# max10adc_v9_02_16chan_frontpanel.net
KiCad netlist of a schematic drawn in EAGLE
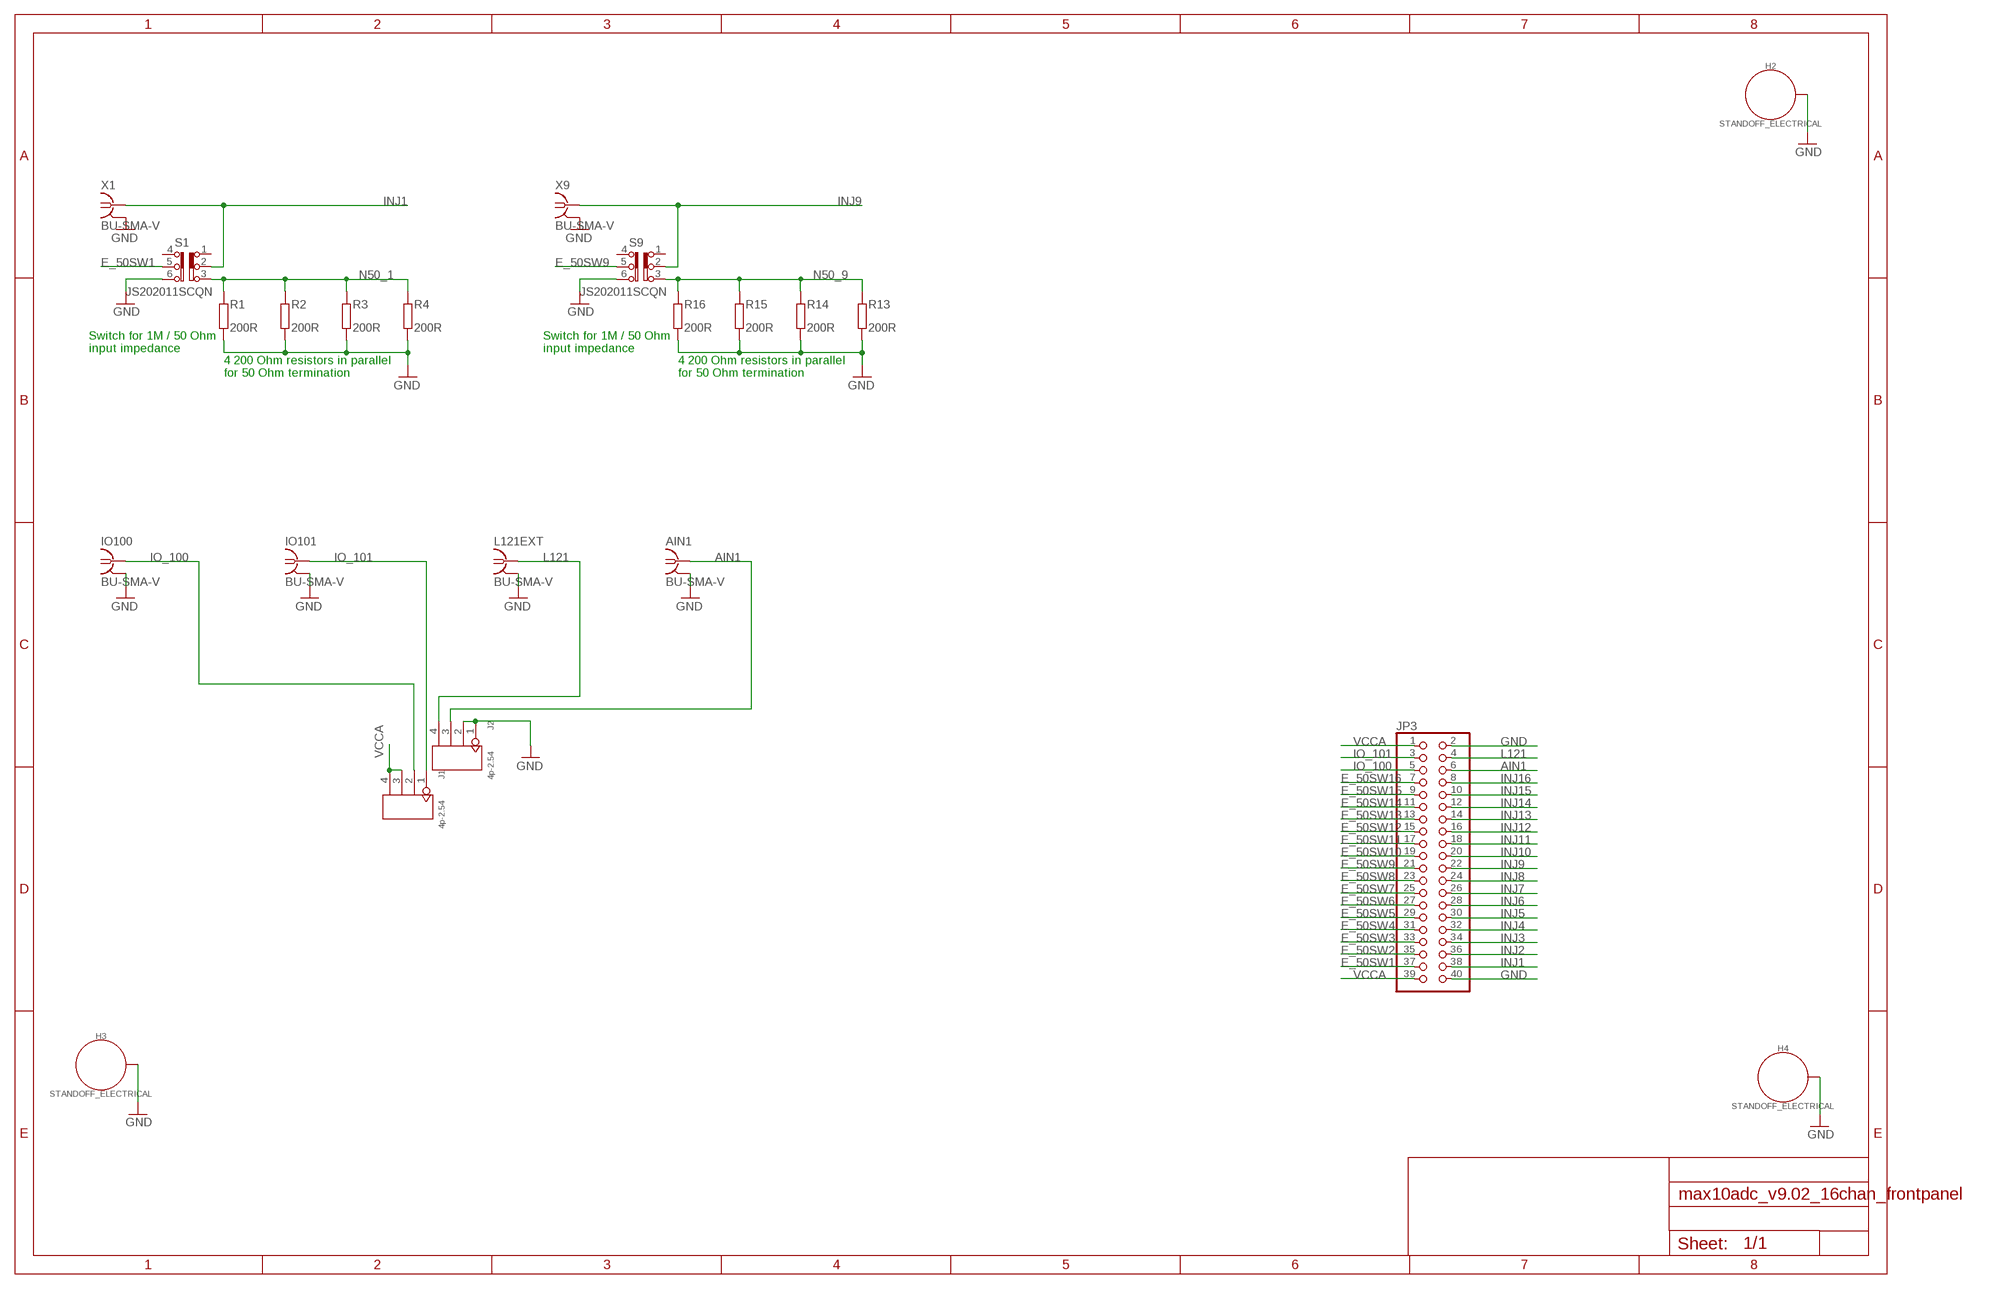
[diagram p0: schematic, sheet 1, part 1 of 2]
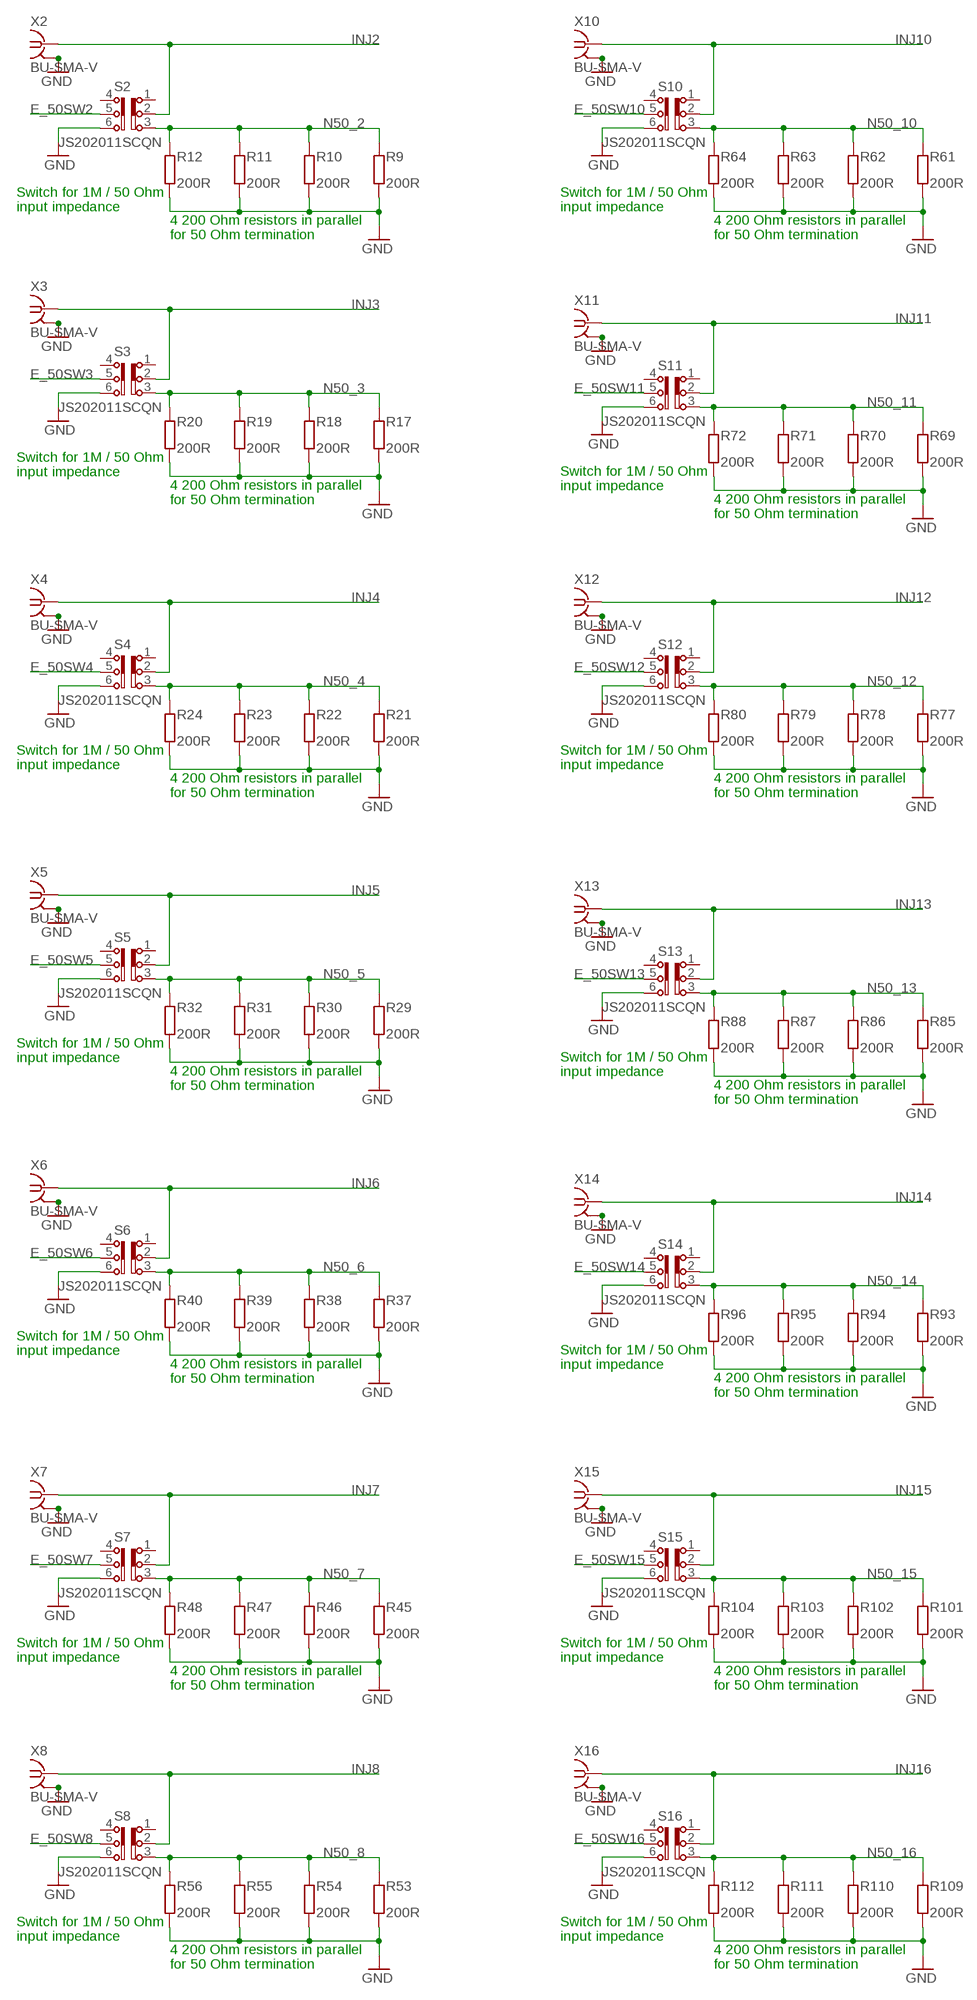
[diagram p1: schematic, sheet 1, part 2 of 2]

(export (version "E")
  (design (tool "Eeschema 10.0.6"))
  (components
    (comp (ref "AIN1")
      (value "BU-SMA-V")
      (footprint "eagle-import:BU-SMA-V")
      (libsource (lib "eagle-import") (part "BU-SMA-V"))
    )
    (comp (ref "H2")
      (value "STANDOFF_ELECTRICAL")
      (footprint "eagle-import:STANDOFF-ELECTRICAL")
      (libsource (lib "eagle-import") (part "STANDOFF_ELECTRICAL"))
    )
    (comp (ref "H3")
      (value "STANDOFF_ELECTRICAL")
      (footprint "eagle-import:STANDOFF-ELECTRICAL")
      (libsource (lib "eagle-import") (part "STANDOFF_ELECTRICAL"))
    )
    (comp (ref "H4")
      (value "STANDOFF_ELECTRICAL")
      (footprint "eagle-import:STANDOFF-ELECTRICAL")
      (libsource (lib "eagle-import") (part "STANDOFF_ELECTRICAL"))
    )
    (comp (ref "IO100")
      (value "BU-SMA-V")
      (footprint "eagle-import:BU-SMA-V")
      (libsource (lib "eagle-import") (part "BU-SMA-V"))
    )
    (comp (ref "IO101")
      (value "BU-SMA-V")
      (footprint "eagle-import:BU-SMA-V")
      (libsource (lib "eagle-import") (part "BU-SMA-V"))
    )
    (comp (ref "J1")
      (value "4p-2.54")
      (footprint "eagle-import:H4-2.54")
      (fields (field (name "MPN") "P125-1104A0BS116A1"))
      (libsource (lib "eagle-import") (part "DIP-BLACK-MALE-HEADER-VERT(4P-2.54)"))
    )
    (comp (ref "J2")
      (value "4p-2.54")
      (footprint "eagle-import:H4-2.54")
      (fields (field (name "MPN") "P125-1104A0BS116A1"))
      (libsource (lib "eagle-import") (part "DIP-BLACK-MALE-HEADER-VERT(4P-2.54)"))
    )
    (comp (ref "JP3")
      (value "PINHD-2X20")
      (footprint "eagle-import:2X20")
      (libsource (lib "eagle-import") (part "PINHD-2X20"))
    )
    (comp (ref "L121EXT")
      (value "BU-SMA-V")
      (footprint "eagle-import:BU-SMA-V")
      (libsource (lib "eagle-import") (part "BU-SMA-V"))
    )
    (comp (ref "R1")
      (value "200R")
      (footprint "eagle-import:R0805")
      (libsource (lib "eagle-import") (part "R-EU_R0805"))
    )
    (comp (ref "R2")
      (value "200R")
      (footprint "eagle-import:R0805")
      (libsource (lib "eagle-import") (part "R-EU_R0805"))
    )
    (comp (ref "R3")
      (value "200R")
      (footprint "eagle-import:R0805")
      (libsource (lib "eagle-import") (part "R-EU_R0805"))
    )
    (comp (ref "R4")
      (value "200R")
      (footprint "eagle-import:R0805")
      (libsource (lib "eagle-import") (part "R-EU_R0805"))
    )
    (comp (ref "R9")
      (value "200R")
      (footprint "eagle-import:R0805")
      (libsource (lib "eagle-import") (part "R-EU_R0805"))
    )
    (comp (ref "R10")
      (value "200R")
      (footprint "eagle-import:R0805")
      (libsource (lib "eagle-import") (part "R-EU_R0805"))
    )
    (comp (ref "R11")
      (value "200R")
      (footprint "eagle-import:R0805")
      (libsource (lib "eagle-import") (part "R-EU_R0805"))
    )
    (comp (ref "R12")
      (value "200R")
      (footprint "eagle-import:R0805")
      (libsource (lib "eagle-import") (part "R-EU_R0805"))
    )
    (comp (ref "R13")
      (value "200R")
      (footprint "eagle-import:R0805")
      (libsource (lib "eagle-import") (part "R-EU_R0805"))
    )
    (comp (ref "R14")
      (value "200R")
      (footprint "eagle-import:R0805")
      (libsource (lib "eagle-import") (part "R-EU_R0805"))
    )
    (comp (ref "R15")
      (value "200R")
      (footprint "eagle-import:R0805")
      (libsource (lib "eagle-import") (part "R-EU_R0805"))
    )
    (comp (ref "R16")
      (value "200R")
      (footprint "eagle-import:R0805")
      (libsource (lib "eagle-import") (part "R-EU_R0805"))
    )
    (comp (ref "R17")
      (value "200R")
      (footprint "eagle-import:R0805")
      (libsource (lib "eagle-import") (part "R-EU_R0805"))
    )
    (comp (ref "R18")
      (value "200R")
      (footprint "eagle-import:R0805")
      (libsource (lib "eagle-import") (part "R-EU_R0805"))
    )
    (comp (ref "R19")
      (value "200R")
      (footprint "eagle-import:R0805")
      (libsource (lib "eagle-import") (part "R-EU_R0805"))
    )
    (comp (ref "R20")
      (value "200R")
      (footprint "eagle-import:R0805")
      (libsource (lib "eagle-import") (part "R-EU_R0805"))
    )
    (comp (ref "R21")
      (value "200R")
      (footprint "eagle-import:R0805")
      (libsource (lib "eagle-import") (part "R-EU_R0805"))
    )
    (comp (ref "R22")
      (value "200R")
      (footprint "eagle-import:R0805")
      (libsource (lib "eagle-import") (part "R-EU_R0805"))
    )
    (comp (ref "R23")
      (value "200R")
      (footprint "eagle-import:R0805")
      (libsource (lib "eagle-import") (part "R-EU_R0805"))
    )
    (comp (ref "R24")
      (value "200R")
      (footprint "eagle-import:R0805")
      (libsource (lib "eagle-import") (part "R-EU_R0805"))
    )
    (comp (ref "R29")
      (value "200R")
      (footprint "eagle-import:R0805")
      (libsource (lib "eagle-import") (part "R-EU_R0805"))
    )
    (comp (ref "R30")
      (value "200R")
      (footprint "eagle-import:R0805")
      (libsource (lib "eagle-import") (part "R-EU_R0805"))
    )
    (comp (ref "R31")
      (value "200R")
      (footprint "eagle-import:R0805")
      (libsource (lib "eagle-import") (part "R-EU_R0805"))
    )
    (comp (ref "R32")
      (value "200R")
      (footprint "eagle-import:R0805")
      (libsource (lib "eagle-import") (part "R-EU_R0805"))
    )
    (comp (ref "R37")
      (value "200R")
      (footprint "eagle-import:R0805")
      (libsource (lib "eagle-import") (part "R-EU_R0805"))
    )
    (comp (ref "R38")
      (value "200R")
      (footprint "eagle-import:R0805")
      (libsource (lib "eagle-import") (part "R-EU_R0805"))
    )
    (comp (ref "R39")
      (value "200R")
      (footprint "eagle-import:R0805")
      (libsource (lib "eagle-import") (part "R-EU_R0805"))
    )
    (comp (ref "R40")
      (value "200R")
      (footprint "eagle-import:R0805")
      (libsource (lib "eagle-import") (part "R-EU_R0805"))
    )
    (comp (ref "R45")
      (value "200R")
      (footprint "eagle-import:R0805")
      (libsource (lib "eagle-import") (part "R-EU_R0805"))
    )
    (comp (ref "R46")
      (value "200R")
      (footprint "eagle-import:R0805")
      (libsource (lib "eagle-import") (part "R-EU_R0805"))
    )
    (comp (ref "R47")
      (value "200R")
      (footprint "eagle-import:R0805")
      (libsource (lib "eagle-import") (part "R-EU_R0805"))
    )
    (comp (ref "R48")
      (value "200R")
      (footprint "eagle-import:R0805")
      (libsource (lib "eagle-import") (part "R-EU_R0805"))
    )
    (comp (ref "R53")
      (value "200R")
      (footprint "eagle-import:R0805")
      (libsource (lib "eagle-import") (part "R-EU_R0805"))
    )
    (comp (ref "R54")
      (value "200R")
      (footprint "eagle-import:R0805")
      (libsource (lib "eagle-import") (part "R-EU_R0805"))
    )
    (comp (ref "R55")
      (value "200R")
      (footprint "eagle-import:R0805")
      (libsource (lib "eagle-import") (part "R-EU_R0805"))
    )
    (comp (ref "R56")
      (value "200R")
      (footprint "eagle-import:R0805")
      (libsource (lib "eagle-import") (part "R-EU_R0805"))
    )
    (comp (ref "R61")
      (value "200R")
      (footprint "eagle-import:R0805")
      (libsource (lib "eagle-import") (part "R-EU_R0805"))
    )
    (comp (ref "R62")
      (value "200R")
      (footprint "eagle-import:R0805")
      (libsource (lib "eagle-import") (part "R-EU_R0805"))
    )
    (comp (ref "R63")
      (value "200R")
      (footprint "eagle-import:R0805")
      (libsource (lib "eagle-import") (part "R-EU_R0805"))
    )
    (comp (ref "R64")
      (value "200R")
      (footprint "eagle-import:R0805")
      (libsource (lib "eagle-import") (part "R-EU_R0805"))
    )
    (comp (ref "R69")
      (value "200R")
      (footprint "eagle-import:R0805")
      (libsource (lib "eagle-import") (part "R-EU_R0805"))
    )
    (comp (ref "R70")
      (value "200R")
      (footprint "eagle-import:R0805")
      (libsource (lib "eagle-import") (part "R-EU_R0805"))
    )
    (comp (ref "R71")
      (value "200R")
      (footprint "eagle-import:R0805")
      (libsource (lib "eagle-import") (part "R-EU_R0805"))
    )
    (comp (ref "R72")
      (value "200R")
      (footprint "eagle-import:R0805")
      (libsource (lib "eagle-import") (part "R-EU_R0805"))
    )
    (comp (ref "R77")
      (value "200R")
      (footprint "eagle-import:R0805")
      (libsource (lib "eagle-import") (part "R-EU_R0805"))
    )
    (comp (ref "R78")
      (value "200R")
      (footprint "eagle-import:R0805")
      (libsource (lib "eagle-import") (part "R-EU_R0805"))
    )
    (comp (ref "R79")
      (value "200R")
      (footprint "eagle-import:R0805")
      (libsource (lib "eagle-import") (part "R-EU_R0805"))
    )
    (comp (ref "R80")
      (value "200R")
      (footprint "eagle-import:R0805")
      (libsource (lib "eagle-import") (part "R-EU_R0805"))
    )
    (comp (ref "R85")
      (value "200R")
      (footprint "eagle-import:R0805")
      (libsource (lib "eagle-import") (part "R-EU_R0805"))
    )
    (comp (ref "R86")
      (value "200R")
      (footprint "eagle-import:R0805")
      (libsource (lib "eagle-import") (part "R-EU_R0805"))
    )
    (comp (ref "R87")
      (value "200R")
      (footprint "eagle-import:R0805")
      (libsource (lib "eagle-import") (part "R-EU_R0805"))
    )
    (comp (ref "R88")
      (value "200R")
      (footprint "eagle-import:R0805")
      (libsource (lib "eagle-import") (part "R-EU_R0805"))
    )
    (comp (ref "R93")
      (value "200R")
      (footprint "eagle-import:R0805")
      (libsource (lib "eagle-import") (part "R-EU_R0805"))
    )
    (comp (ref "R94")
      (value "200R")
      (footprint "eagle-import:R0805")
      (libsource (lib "eagle-import") (part "R-EU_R0805"))
    )
    (comp (ref "R95")
      (value "200R")
      (footprint "eagle-import:R0805")
      (libsource (lib "eagle-import") (part "R-EU_R0805"))
    )
    (comp (ref "R96")
      (value "200R")
      (footprint "eagle-import:R0805")
      (libsource (lib "eagle-import") (part "R-EU_R0805"))
    )
    (comp (ref "R101")
      (value "200R")
      (footprint "eagle-import:R0805")
      (libsource (lib "eagle-import") (part "R-EU_R0805"))
    )
    (comp (ref "R102")
      (value "200R")
      (footprint "eagle-import:R0805")
      (libsource (lib "eagle-import") (part "R-EU_R0805"))
    )
    (comp (ref "R103")
      (value "200R")
      (footprint "eagle-import:R0805")
      (libsource (lib "eagle-import") (part "R-EU_R0805"))
    )
    (comp (ref "R104")
      (value "200R")
      (footprint "eagle-import:R0805")
      (libsource (lib "eagle-import") (part "R-EU_R0805"))
    )
    (comp (ref "R109")
      (value "200R")
      (footprint "eagle-import:R0805")
      (libsource (lib "eagle-import") (part "R-EU_R0805"))
    )
    (comp (ref "R110")
      (value "200R")
      (footprint "eagle-import:R0805")
      (libsource (lib "eagle-import") (part "R-EU_R0805"))
    )
    (comp (ref "R111")
      (value "200R")
      (footprint "eagle-import:R0805")
      (libsource (lib "eagle-import") (part "R-EU_R0805"))
    )
    (comp (ref "R112")
      (value "200R")
      (footprint "eagle-import:R0805")
      (libsource (lib "eagle-import") (part "R-EU_R0805"))
    )
    (comp (ref "S1")
      (value "JS202011SCQN")
      (footprint "eagle-import:JS202011SCQN")
      (libsource (lib "eagle-import") (part "JS202011SCQN"))
    )
    (comp (ref "S2")
      (value "JS202011SCQN")
      (footprint "eagle-import:JS202011SCQN")
      (libsource (lib "eagle-import") (part "JS202011SCQN"))
    )
    (comp (ref "S3")
      (value "JS202011SCQN")
      (footprint "eagle-import:JS202011SCQN")
      (libsource (lib "eagle-import") (part "JS202011SCQN"))
    )
    (comp (ref "S4")
      (value "JS202011SCQN")
      (footprint "eagle-import:JS202011SCQN")
      (libsource (lib "eagle-import") (part "JS202011SCQN"))
    )
    (comp (ref "S5")
      (value "JS202011SCQN")
      (footprint "eagle-import:JS202011SCQN")
      (libsource (lib "eagle-import") (part "JS202011SCQN"))
    )
    (comp (ref "S6")
      (value "JS202011SCQN")
      (footprint "eagle-import:JS202011SCQN")
      (libsource (lib "eagle-import") (part "JS202011SCQN"))
    )
    (comp (ref "S7")
      (value "JS202011SCQN")
      (footprint "eagle-import:JS202011SCQN")
      (libsource (lib "eagle-import") (part "JS202011SCQN"))
    )
    (comp (ref "S8")
      (value "JS202011SCQN")
      (footprint "eagle-import:JS202011SCQN")
      (libsource (lib "eagle-import") (part "JS202011SCQN"))
    )
    (comp (ref "S9")
      (value "JS202011SCQN")
      (footprint "eagle-import:JS202011SCQN")
      (libsource (lib "eagle-import") (part "JS202011SCQN"))
    )
    (comp (ref "S10")
      (value "JS202011SCQN")
      (footprint "eagle-import:JS202011SCQN")
      (libsource (lib "eagle-import") (part "JS202011SCQN"))
    )
    (comp (ref "S11")
      (value "JS202011SCQN")
      (footprint "eagle-import:JS202011SCQN")
      (libsource (lib "eagle-import") (part "JS202011SCQN"))
    )
    (comp (ref "S12")
      (value "JS202011SCQN")
      (footprint "eagle-import:JS202011SCQN")
      (libsource (lib "eagle-import") (part "JS202011SCQN"))
    )
    (comp (ref "S13")
      (value "JS202011SCQN")
      (footprint "eagle-import:JS202011SCQN")
      (libsource (lib "eagle-import") (part "JS202011SCQN"))
    )
    (comp (ref "S14")
      (value "JS202011SCQN")
      (footprint "eagle-import:JS202011SCQN")
      (libsource (lib "eagle-import") (part "JS202011SCQN"))
    )
    (comp (ref "S15")
      (value "JS202011SCQN")
      (footprint "eagle-import:JS202011SCQN")
      (libsource (lib "eagle-import") (part "JS202011SCQN"))
    )
    (comp (ref "S16")
      (value "JS202011SCQN")
      (footprint "eagle-import:JS202011SCQN")
      (libsource (lib "eagle-import") (part "JS202011SCQN"))
    )
    (comp (ref "X1")
      (value "BU-SMA-V")
      (footprint "eagle-import:BU-SMA-V")
      (libsource (lib "eagle-import") (part "BU-SMA-V"))
    )
    (comp (ref "X2")
      (value "BU-SMA-V")
      (footprint "eagle-import:BU-SMA-V")
      (libsource (lib "eagle-import") (part "BU-SMA-V"))
    )
    (comp (ref "X3")
      (value "BU-SMA-V")
      (footprint "eagle-import:BU-SMA-V")
      (libsource (lib "eagle-import") (part "BU-SMA-V"))
    )
    (comp (ref "X4")
      (value "BU-SMA-V")
      (footprint "eagle-import:BU-SMA-V")
      (libsource (lib "eagle-import") (part "BU-SMA-V"))
    )
    (comp (ref "X5")
      (value "BU-SMA-V")
      (footprint "eagle-import:BU-SMA-V")
      (libsource (lib "eagle-import") (part "BU-SMA-V"))
    )
    (comp (ref "X6")
      (value "BU-SMA-V")
      (footprint "eagle-import:BU-SMA-V")
      (libsource (lib "eagle-import") (part "BU-SMA-V"))
    )
    (comp (ref "X7")
      (value "BU-SMA-V")
      (footprint "eagle-import:BU-SMA-V")
      (libsource (lib "eagle-import") (part "BU-SMA-V"))
    )
    (comp (ref "X8")
      (value "BU-SMA-V")
      (footprint "eagle-import:BU-SMA-V")
      (libsource (lib "eagle-import") (part "BU-SMA-V"))
    )
    (comp (ref "X9")
      (value "BU-SMA-V")
      (footprint "eagle-import:BU-SMA-V")
      (libsource (lib "eagle-import") (part "BU-SMA-V"))
    )
    (comp (ref "X10")
      (value "BU-SMA-V")
      (footprint "eagle-import:BU-SMA-V")
      (libsource (lib "eagle-import") (part "BU-SMA-V"))
    )
    (comp (ref "X11")
      (value "BU-SMA-V")
      (footprint "eagle-import:BU-SMA-V")
      (libsource (lib "eagle-import") (part "BU-SMA-V"))
    )
    (comp (ref "X12")
      (value "BU-SMA-V")
      (footprint "eagle-import:BU-SMA-V")
      (libsource (lib "eagle-import") (part "BU-SMA-V"))
    )
    (comp (ref "X13")
      (value "BU-SMA-V")
      (footprint "eagle-import:BU-SMA-V")
      (libsource (lib "eagle-import") (part "BU-SMA-V"))
    )
    (comp (ref "X14")
      (value "BU-SMA-V")
      (footprint "eagle-import:BU-SMA-V")
      (libsource (lib "eagle-import") (part "BU-SMA-V"))
    )
    (comp (ref "X15")
      (value "BU-SMA-V")
      (footprint "eagle-import:BU-SMA-V")
      (libsource (lib "eagle-import") (part "BU-SMA-V"))
    )
    (comp (ref "X16")
      (value "BU-SMA-V")
      (footprint "eagle-import:BU-SMA-V")
      (libsource (lib "eagle-import") (part "BU-SMA-V"))
    )
  )
  (nets
    (net (code "1") (name "/AIN1") (class "Default")
      (node (ref "AIN1") (pin "1") (pinfunction "1_1") (pintype "passive"))
      (node (ref "J2") (pin "3") (pinfunction "P$3_3") (pintype "bidirectional"))
      (node (ref "JP3") (pin "6") (pinfunction "6_6") (pintype "passive"))
    )
    (net (code "2") (name "/E_50SW1") (class "Default")
      (node (ref "JP3") (pin "37") (pinfunction "37_37") (pintype "passive"))
      (node (ref "S1") (pin "5") (pinfunction "5_5") (pintype "passive"))
    )
    (net (code "3") (name "/E_50SW2") (class "Default")
      (node (ref "JP3") (pin "35") (pinfunction "35_35") (pintype "passive"))
      (node (ref "S2") (pin "5") (pinfunction "5_5") (pintype "passive"))
    )
    (net (code "4") (name "/E_50SW3") (class "Default")
      (node (ref "JP3") (pin "33") (pinfunction "33_33") (pintype "passive"))
      (node (ref "S3") (pin "5") (pinfunction "5_5") (pintype "passive"))
    )
    (net (code "5") (name "/E_50SW4") (class "Default")
      (node (ref "JP3") (pin "31") (pinfunction "31_31") (pintype "passive"))
      (node (ref "S4") (pin "5") (pinfunction "5_5") (pintype "passive"))
    )
    (net (code "6") (name "/E_50SW5") (class "Default")
      (node (ref "JP3") (pin "29") (pinfunction "29_29") (pintype "passive"))
      (node (ref "S5") (pin "5") (pinfunction "5_5") (pintype "passive"))
    )
    (net (code "7") (name "/E_50SW6") (class "Default")
      (node (ref "JP3") (pin "27") (pinfunction "27_27") (pintype "passive"))
      (node (ref "S6") (pin "5") (pinfunction "5_5") (pintype "passive"))
    )
    (net (code "8") (name "/E_50SW7") (class "Default")
      (node (ref "JP3") (pin "25") (pinfunction "25_25") (pintype "passive"))
      (node (ref "S7") (pin "5") (pinfunction "5_5") (pintype "passive"))
    )
    (net (code "9") (name "/E_50SW8") (class "Default")
      (node (ref "JP3") (pin "23") (pinfunction "23_23") (pintype "passive"))
      (node (ref "S8") (pin "5") (pinfunction "5_5") (pintype "passive"))
    )
    (net (code "10") (name "/E_50SW9") (class "Default")
      (node (ref "JP3") (pin "21") (pinfunction "21_21") (pintype "passive"))
      (node (ref "S9") (pin "5") (pinfunction "5_5") (pintype "passive"))
    )
    (net (code "11") (name "/E_50SW10") (class "Default")
      (node (ref "JP3") (pin "19") (pinfunction "19_19") (pintype "passive"))
      (node (ref "S10") (pin "5") (pinfunction "5_5") (pintype "passive"))
    )
    (net (code "12") (name "/E_50SW11") (class "Default")
      (node (ref "JP3") (pin "17") (pinfunction "17_17") (pintype "passive"))
      (node (ref "S11") (pin "5") (pinfunction "5_5") (pintype "passive"))
    )
    (net (code "13") (name "/E_50SW12") (class "Default")
      (node (ref "JP3") (pin "15") (pinfunction "15_15") (pintype "passive"))
      (node (ref "S12") (pin "5") (pinfunction "5_5") (pintype "passive"))
    )
    (net (code "14") (name "/E_50SW13") (class "Default")
      (node (ref "JP3") (pin "13") (pinfunction "13_13") (pintype "passive"))
      (node (ref "S13") (pin "5") (pinfunction "5_5") (pintype "passive"))
    )
    (net (code "15") (name "/E_50SW14") (class "Default")
      (node (ref "JP3") (pin "11") (pinfunction "11_11") (pintype "passive"))
      (node (ref "S14") (pin "5") (pinfunction "5_5") (pintype "passive"))
    )
    (net (code "16") (name "/E_50SW15") (class "Default")
      (node (ref "JP3") (pin "9") (pinfunction "9_9") (pintype "passive"))
      (node (ref "S15") (pin "5") (pinfunction "5_5") (pintype "passive"))
    )
    (net (code "17") (name "/E_50SW16") (class "Default")
      (node (ref "JP3") (pin "7") (pinfunction "7_7") (pintype "passive"))
      (node (ref "S16") (pin "5") (pinfunction "5_5") (pintype "passive"))
    )
    (net (code "18") (name "/INJ1") (class "Default")
      (node (ref "JP3") (pin "38") (pinfunction "38_38") (pintype "passive"))
      (node (ref "S1") (pin "2") (pinfunction "2_2") (pintype "passive"))
      (node (ref "X1") (pin "1") (pinfunction "1_1") (pintype "passive"))
    )
    (net (code "19") (name "/INJ2") (class "Default")
      (node (ref "JP3") (pin "36") (pinfunction "36_36") (pintype "passive"))
      (node (ref "S2") (pin "2") (pinfunction "2_2") (pintype "passive"))
      (node (ref "X2") (pin "1") (pinfunction "1_1") (pintype "passive"))
    )
    (net (code "20") (name "/INJ3") (class "Default")
      (node (ref "JP3") (pin "34") (pinfunction "34_34") (pintype "passive"))
      (node (ref "S3") (pin "2") (pinfunction "2_2") (pintype "passive"))
      (node (ref "X3") (pin "1") (pinfunction "1_1") (pintype "passive"))
    )
    (net (code "21") (name "/INJ4") (class "Default")
      (node (ref "JP3") (pin "32") (pinfunction "32_32") (pintype "passive"))
      (node (ref "S4") (pin "2") (pinfunction "2_2") (pintype "passive"))
      (node (ref "X4") (pin "1") (pinfunction "1_1") (pintype "passive"))
    )
    (net (code "22") (name "/INJ5") (class "Default")
      (node (ref "JP3") (pin "30") (pinfunction "30_30") (pintype "passive"))
      (node (ref "S5") (pin "2") (pinfunction "2_2") (pintype "passive"))
      (node (ref "X5") (pin "1") (pinfunction "1_1") (pintype "passive"))
    )
    (net (code "23") (name "/INJ6") (class "Default")
      (node (ref "JP3") (pin "28") (pinfunction "28_28") (pintype "passive"))
      (node (ref "S6") (pin "2") (pinfunction "2_2") (pintype "passive"))
      (node (ref "X6") (pin "1") (pinfunction "1_1") (pintype "passive"))
    )
    (net (code "24") (name "/INJ7") (class "Default")
      (node (ref "JP3") (pin "26") (pinfunction "26_26") (pintype "passive"))
      (node (ref "S7") (pin "2") (pinfunction "2_2") (pintype "passive"))
      (node (ref "X7") (pin "1") (pinfunction "1_1") (pintype "passive"))
    )
    (net (code "25") (name "/INJ8") (class "Default")
      (node (ref "JP3") (pin "24") (pinfunction "24_24") (pintype "passive"))
      (node (ref "S8") (pin "2") (pinfunction "2_2") (pintype "passive"))
      (node (ref "X8") (pin "1") (pinfunction "1_1") (pintype "passive"))
    )
    (net (code "26") (name "/INJ9") (class "Default")
      (node (ref "JP3") (pin "22") (pinfunction "22_22") (pintype "passive"))
      (node (ref "S9") (pin "2") (pinfunction "2_2") (pintype "passive"))
      (node (ref "X9") (pin "1") (pinfunction "1_1") (pintype "passive"))
    )
    (net (code "27") (name "/INJ10") (class "Default")
      (node (ref "JP3") (pin "20") (pinfunction "20_20") (pintype "passive"))
      (node (ref "S10") (pin "2") (pinfunction "2_2") (pintype "passive"))
      (node (ref "X10") (pin "1") (pinfunction "1_1") (pintype "passive"))
    )
    (net (code "28") (name "/INJ11") (class "Default")
      (node (ref "JP3") (pin "18") (pinfunction "18_18") (pintype "passive"))
      (node (ref "S11") (pin "2") (pinfunction "2_2") (pintype "passive"))
      (node (ref "X11") (pin "1") (pinfunction "1_1") (pintype "passive"))
    )
    (net (code "29") (name "/INJ12") (class "Default")
      (node (ref "JP3") (pin "16") (pinfunction "16_16") (pintype "passive"))
      (node (ref "S12") (pin "2") (pinfunction "2_2") (pintype "passive"))
      (node (ref "X12") (pin "1") (pinfunction "1_1") (pintype "passive"))
    )
    (net (code "30") (name "/INJ13") (class "Default")
      (node (ref "JP3") (pin "14") (pinfunction "14_14") (pintype "passive"))
      (node (ref "S13") (pin "2") (pinfunction "2_2") (pintype "passive"))
      (node (ref "X13") (pin "1") (pinfunction "1_1") (pintype "passive"))
    )
    (net (code "31") (name "/INJ14") (class "Default")
      (node (ref "JP3") (pin "12") (pinfunction "12_12") (pintype "passive"))
      (node (ref "S14") (pin "2") (pinfunction "2_2") (pintype "passive"))
      (node (ref "X14") (pin "1") (pinfunction "1_1") (pintype "passive"))
    )
    (net (code "32") (name "/INJ15") (class "Default")
      (node (ref "JP3") (pin "10") (pinfunction "10_10") (pintype "passive"))
      (node (ref "S15") (pin "2") (pinfunction "2_2") (pintype "passive"))
      (node (ref "X15") (pin "1") (pinfunction "1_1") (pintype "passive"))
    )
    (net (code "33") (name "/INJ16") (class "Default")
      (node (ref "JP3") (pin "8") (pinfunction "8_8") (pintype "passive"))
      (node (ref "S16") (pin "2") (pinfunction "2_2") (pintype "passive"))
      (node (ref "X16") (pin "1") (pinfunction "1_1") (pintype "passive"))
    )
    (net (code "34") (name "/IO_100") (class "Default")
      (node (ref "IO100") (pin "1") (pinfunction "1_1") (pintype "passive"))
      (node (ref "J1") (pin "2") (pinfunction "P$2_2") (pintype "bidirectional"))
      (node (ref "JP3") (pin "5") (pinfunction "5_5") (pintype "passive"))
    )
    (net (code "35") (name "/IO_101") (class "Default")
      (node (ref "IO101") (pin "1") (pinfunction "1_1") (pintype "passive"))
      (node (ref "J1") (pin "1") (pinfunction "P$1_1") (pintype "bidirectional"))
      (node (ref "JP3") (pin "3") (pinfunction "3_3") (pintype "passive"))
    )
    (net (code "36") (name "/L121") (class "Default")
      (node (ref "J2") (pin "4") (pinfunction "P$4_4") (pintype "bidirectional"))
      (node (ref "JP3") (pin "4") (pinfunction "4_4") (pintype "passive"))
      (node (ref "L121EXT") (pin "1") (pinfunction "1_1") (pintype "passive"))
    )
    (net (code "37") (name "/N50_1") (class "Default")
      (node (ref "R1") (pin "1") (pinfunction "1_1") (pintype "passive"))
      (node (ref "R2") (pin "1") (pinfunction "1_1") (pintype "passive"))
      (node (ref "R3") (pin "1") (pinfunction "1_1") (pintype "passive"))
      (node (ref "R4") (pin "1") (pinfunction "1_1") (pintype "passive"))
      (node (ref "S1") (pin "3") (pinfunction "3_3") (pintype "passive"))
    )
    (net (code "38") (name "/N50_2") (class "Default")
      (node (ref "R10") (pin "1") (pinfunction "1_1") (pintype "passive"))
      (node (ref "R11") (pin "1") (pinfunction "1_1") (pintype "passive"))
      (node (ref "R12") (pin "1") (pinfunction "1_1") (pintype "passive"))
      (node (ref "R9") (pin "1") (pinfunction "1_1") (pintype "passive"))
      (node (ref "S2") (pin "3") (pinfunction "3_3") (pintype "passive"))
    )
    (net (code "39") (name "/N50_3") (class "Default")
      (node (ref "R17") (pin "1") (pinfunction "1_1") (pintype "passive"))
      (node (ref "R18") (pin "1") (pinfunction "1_1") (pintype "passive"))
      (node (ref "R19") (pin "1") (pinfunction "1_1") (pintype "passive"))
      (node (ref "R20") (pin "1") (pinfunction "1_1") (pintype "passive"))
      (node (ref "S3") (pin "3") (pinfunction "3_3") (pintype "passive"))
    )
    (net (code "40") (name "/N50_4") (class "Default")
      (node (ref "R21") (pin "1") (pinfunction "1_1") (pintype "passive"))
      (node (ref "R22") (pin "1") (pinfunction "1_1") (pintype "passive"))
      (node (ref "R23") (pin "1") (pinfunction "1_1") (pintype "passive"))
      (node (ref "R24") (pin "1") (pinfunction "1_1") (pintype "passive"))
      (node (ref "S4") (pin "3") (pinfunction "3_3") (pintype "passive"))
    )
    (net (code "41") (name "/N50_5") (class "Default")
      (node (ref "R29") (pin "1") (pinfunction "1_1") (pintype "passive"))
      (node (ref "R30") (pin "1") (pinfunction "1_1") (pintype "passive"))
      (node (ref "R31") (pin "1") (pinfunction "1_1") (pintype "passive"))
      (node (ref "R32") (pin "1") (pinfunction "1_1") (pintype "passive"))
      (node (ref "S5") (pin "3") (pinfunction "3_3") (pintype "passive"))
    )
    (net (code "42") (name "/N50_6") (class "Default")
      (node (ref "R37") (pin "1") (pinfunction "1_1") (pintype "passive"))
      (node (ref "R38") (pin "1") (pinfunction "1_1") (pintype "passive"))
      (node (ref "R39") (pin "1") (pinfunction "1_1") (pintype "passive"))
      (node (ref "R40") (pin "1") (pinfunction "1_1") (pintype "passive"))
      (node (ref "S6") (pin "3") (pinfunction "3_3") (pintype "passive"))
    )
    (net (code "43") (name "/N50_7") (class "Default")
      (node (ref "R45") (pin "1") (pinfunction "1_1") (pintype "passive"))
      (node (ref "R46") (pin "1") (pinfunction "1_1") (pintype "passive"))
      (node (ref "R47") (pin "1") (pinfunction "1_1") (pintype "passive"))
      (node (ref "R48") (pin "1") (pinfunction "1_1") (pintype "passive"))
      (node (ref "S7") (pin "3") (pinfunction "3_3") (pintype "passive"))
    )
    (net (code "44") (name "/N50_8") (class "Default")
      (node (ref "R53") (pin "1") (pinfunction "1_1") (pintype "passive"))
      (node (ref "R54") (pin "1") (pinfunction "1_1") (pintype "passive"))
      (node (ref "R55") (pin "1") (pinfunction "1_1") (pintype "passive"))
      (node (ref "R56") (pin "1") (pinfunction "1_1") (pintype "passive"))
      (node (ref "S8") (pin "3") (pinfunction "3_3") (pintype "passive"))
    )
    (net (code "45") (name "/N50_9") (class "Default")
      (node (ref "R13") (pin "1") (pinfunction "1_1") (pintype "passive"))
      (node (ref "R14") (pin "1") (pinfunction "1_1") (pintype "passive"))
      (node (ref "R15") (pin "1") (pinfunction "1_1") (pintype "passive"))
      (node (ref "R16") (pin "1") (pinfunction "1_1") (pintype "passive"))
      (node (ref "S9") (pin "3") (pinfunction "3_3") (pintype "passive"))
    )
    (net (code "46") (name "/N50_10") (class "Default")
      (node (ref "R61") (pin "1") (pinfunction "1_1") (pintype "passive"))
      (node (ref "R62") (pin "1") (pinfunction "1_1") (pintype "passive"))
      (node (ref "R63") (pin "1") (pinfunction "1_1") (pintype "passive"))
      (node (ref "R64") (pin "1") (pinfunction "1_1") (pintype "passive"))
      (node (ref "S10") (pin "3") (pinfunction "3_3") (pintype "passive"))
    )
    (net (code "47") (name "/N50_11") (class "Default")
      (node (ref "R69") (pin "1") (pinfunction "1_1") (pintype "passive"))
      (node (ref "R70") (pin "1") (pinfunction "1_1") (pintype "passive"))
      (node (ref "R71") (pin "1") (pinfunction "1_1") (pintype "passive"))
      (node (ref "R72") (pin "1") (pinfunction "1_1") (pintype "passive"))
      (node (ref "S11") (pin "3") (pinfunction "3_3") (pintype "passive"))
    )
    (net (code "48") (name "/N50_12") (class "Default")
      (node (ref "R77") (pin "1") (pinfunction "1_1") (pintype "passive"))
      (node (ref "R78") (pin "1") (pinfunction "1_1") (pintype "passive"))
      (node (ref "R79") (pin "1") (pinfunction "1_1") (pintype "passive"))
      (node (ref "R80") (pin "1") (pinfunction "1_1") (pintype "passive"))
      (node (ref "S12") (pin "3") (pinfunction "3_3") (pintype "passive"))
    )
    (net (code "49") (name "/N50_13") (class "Default")
      (node (ref "R85") (pin "1") (pinfunction "1_1") (pintype "passive"))
      (node (ref "R86") (pin "1") (pinfunction "1_1") (pintype "passive"))
      (node (ref "R87") (pin "1") (pinfunction "1_1") (pintype "passive"))
      (node (ref "R88") (pin "1") (pinfunction "1_1") (pintype "passive"))
      (node (ref "S13") (pin "3") (pinfunction "3_3") (pintype "passive"))
    )
    (net (code "50") (name "/N50_14") (class "Default")
      (node (ref "R93") (pin "1") (pinfunction "1_1") (pintype "passive"))
      (node (ref "R94") (pin "1") (pinfunction "1_1") (pintype "passive"))
      (node (ref "R95") (pin "1") (pinfunction "1_1") (pintype "passive"))
      (node (ref "R96") (pin "1") (pinfunction "1_1") (pintype "passive"))
      (node (ref "S14") (pin "3") (pinfunction "3_3") (pintype "passive"))
    )
    (net (code "51") (name "/N50_15") (class "Default")
      (node (ref "R101") (pin "1") (pinfunction "1_1") (pintype "passive"))
      (node (ref "R102") (pin "1") (pinfunction "1_1") (pintype "passive"))
      (node (ref "R103") (pin "1") (pinfunction "1_1") (pintype "passive"))
      (node (ref "R104") (pin "1") (pinfunction "1_1") (pintype "passive"))
      (node (ref "S15") (pin "3") (pinfunction "3_3") (pintype "passive"))
    )
    (net (code "52") (name "/N50_16") (class "Default")
      (node (ref "R109") (pin "1") (pinfunction "1_1") (pintype "passive"))
      (node (ref "R110") (pin "1") (pinfunction "1_1") (pintype "passive"))
      (node (ref "R111") (pin "1") (pinfunction "1_1") (pintype "passive"))
      (node (ref "R112") (pin "1") (pinfunction "1_1") (pintype "passive"))
      (node (ref "S16") (pin "3") (pinfunction "3_3") (pintype "passive"))
    )
    (net (code "53") (name "/VCCA") (class "Default")
      (node (ref "J1") (pin "3") (pinfunction "P$3_3") (pintype "bidirectional"))
      (node (ref "J1") (pin "4") (pinfunction "P$4_4") (pintype "bidirectional"))
      (node (ref "JP3") (pin "1") (pinfunction "1_1") (pintype "passive"))
      (node (ref "JP3") (pin "39") (pinfunction "39_39") (pintype "passive"))
    )
    (net (code "54") (name "GND") (class "Default")
      (node (ref "AIN1") (pin "2") (pinfunction "2_2") (pintype "passive"))
      (node (ref "AIN1") (pin "3") (pinfunction "2_3") (pintype "passive"))
      (node (ref "AIN1") (pin "4") (pinfunction "2_4") (pintype "passive"))
      (node (ref "AIN1") (pin "5") (pinfunction "2_5") (pintype "passive"))
      (node (ref "H2") (pin "P1") (pinfunction "P$1_P1") (pintype "bidirectional"))
      (node (ref "H3") (pin "P1") (pinfunction "P$1_P1") (pintype "bidirectional"))
      (node (ref "H4") (pin "P1") (pinfunction "P$1_P1") (pintype "bidirectional"))
      (node (ref "IO100") (pin "2") (pinfunction "2_2") (pintype "passive"))
      (node (ref "IO100") (pin "3") (pinfunction "2_3") (pintype "passive"))
      (node (ref "IO100") (pin "4") (pinfunction "2_4") (pintype "passive"))
      (node (ref "IO100") (pin "5") (pinfunction "2_5") (pintype "passive"))
      (node (ref "IO101") (pin "2") (pinfunction "2_2") (pintype "passive"))
      (node (ref "IO101") (pin "3") (pinfunction "2_3") (pintype "passive"))
      (node (ref "IO101") (pin "4") (pinfunction "2_4") (pintype "passive"))
      (node (ref "IO101") (pin "5") (pinfunction "2_5") (pintype "passive"))
      (node (ref "J2") (pin "1") (pinfunction "P$1_1") (pintype "bidirectional"))
      (node (ref "J2") (pin "2") (pinfunction "P$2_2") (pintype "bidirectional"))
      (node (ref "JP3") (pin "2") (pinfunction "2_2") (pintype "passive"))
      (node (ref "JP3") (pin "40") (pinfunction "40_40") (pintype "passive"))
      (node (ref "L121EXT") (pin "2") (pinfunction "2_2") (pintype "passive"))
      (node (ref "L121EXT") (pin "3") (pinfunction "2_3") (pintype "passive"))
      (node (ref "L121EXT") (pin "4") (pinfunction "2_4") (pintype "passive"))
      (node (ref "L121EXT") (pin "5") (pinfunction "2_5") (pintype "passive"))
      (node (ref "R1") (pin "2") (pinfunction "2_2") (pintype "passive"))
      (node (ref "R10") (pin "2") (pinfunction "2_2") (pintype "passive"))
      (node (ref "R101") (pin "2") (pinfunction "2_2") (pintype "passive"))
      (node (ref "R102") (pin "2") (pinfunction "2_2") (pintype "passive"))
      (node (ref "R103") (pin "2") (pinfunction "2_2") (pintype "passive"))
      (node (ref "R104") (pin "2") (pinfunction "2_2") (pintype "passive"))
      (node (ref "R109") (pin "2") (pinfunction "2_2") (pintype "passive"))
      (node (ref "R11") (pin "2") (pinfunction "2_2") (pintype "passive"))
      (node (ref "R110") (pin "2") (pinfunction "2_2") (pintype "passive"))
      (node (ref "R111") (pin "2") (pinfunction "2_2") (pintype "passive"))
      (node (ref "R112") (pin "2") (pinfunction "2_2") (pintype "passive"))
      (node (ref "R12") (pin "2") (pinfunction "2_2") (pintype "passive"))
      (node (ref "R13") (pin "2") (pinfunction "2_2") (pintype "passive"))
      (node (ref "R14") (pin "2") (pinfunction "2_2") (pintype "passive"))
      (node (ref "R15") (pin "2") (pinfunction "2_2") (pintype "passive"))
      (node (ref "R16") (pin "2") (pinfunction "2_2") (pintype "passive"))
      (node (ref "R17") (pin "2") (pinfunction "2_2") (pintype "passive"))
      (node (ref "R18") (pin "2") (pinfunction "2_2") (pintype "passive"))
      (node (ref "R19") (pin "2") (pinfunction "2_2") (pintype "passive"))
      (node (ref "R2") (pin "2") (pinfunction "2_2") (pintype "passive"))
      (node (ref "R20") (pin "2") (pinfunction "2_2") (pintype "passive"))
      (node (ref "R21") (pin "2") (pinfunction "2_2") (pintype "passive"))
      (node (ref "R22") (pin "2") (pinfunction "2_2") (pintype "passive"))
      (node (ref "R23") (pin "2") (pinfunction "2_2") (pintype "passive"))
      (node (ref "R24") (pin "2") (pinfunction "2_2") (pintype "passive"))
      (node (ref "R29") (pin "2") (pinfunction "2_2") (pintype "passive"))
      (node (ref "R3") (pin "2") (pinfunction "2_2") (pintype "passive"))
      (node (ref "R30") (pin "2") (pinfunction "2_2") (pintype "passive"))
      (node (ref "R31") (pin "2") (pinfunction "2_2") (pintype "passive"))
      (node (ref "R32") (pin "2") (pinfunction "2_2") (pintype "passive"))
      (node (ref "R37") (pin "2") (pinfunction "2_2") (pintype "passive"))
      (node (ref "R38") (pin "2") (pinfunction "2_2") (pintype "passive"))
      (node (ref "R39") (pin "2") (pinfunction "2_2") (pintype "passive"))
      (node (ref "R4") (pin "2") (pinfunction "2_2") (pintype "passive"))
      (node (ref "R40") (pin "2") (pinfunction "2_2") (pintype "passive"))
      (node (ref "R45") (pin "2") (pinfunction "2_2") (pintype "passive"))
      (node (ref "R46") (pin "2") (pinfunction "2_2") (pintype "passive"))
      (node (ref "R47") (pin "2") (pinfunction "2_2") (pintype "passive"))
      (node (ref "R48") (pin "2") (pinfunction "2_2") (pintype "passive"))
      (node (ref "R53") (pin "2") (pinfunction "2_2") (pintype "passive"))
      (node (ref "R54") (pin "2") (pinfunction "2_2") (pintype "passive"))
      (node (ref "R55") (pin "2") (pinfunction "2_2") (pintype "passive"))
      (node (ref "R56") (pin "2") (pinfunction "2_2") (pintype "passive"))
      (node (ref "R61") (pin "2") (pinfunction "2_2") (pintype "passive"))
      (node (ref "R62") (pin "2") (pinfunction "2_2") (pintype "passive"))
      (node (ref "R63") (pin "2") (pinfunction "2_2") (pintype "passive"))
      (node (ref "R64") (pin "2") (pinfunction "2_2") (pintype "passive"))
      (node (ref "R69") (pin "2") (pinfunction "2_2") (pintype "passive"))
      (node (ref "R70") (pin "2") (pinfunction "2_2") (pintype "passive"))
      (node (ref "R71") (pin "2") (pinfunction "2_2") (pintype "passive"))
      (node (ref "R72") (pin "2") (pinfunction "2_2") (pintype "passive"))
      (node (ref "R77") (pin "2") (pinfunction "2_2") (pintype "passive"))
      (node (ref "R78") (pin "2") (pinfunction "2_2") (pintype "passive"))
      (node (ref "R79") (pin "2") (pinfunction "2_2") (pintype "passive"))
      (node (ref "R80") (pin "2") (pinfunction "2_2") (pintype "passive"))
      (node (ref "R85") (pin "2") (pinfunction "2_2") (pintype "passive"))
      (node (ref "R86") (pin "2") (pinfunction "2_2") (pintype "passive"))
      (node (ref "R87") (pin "2") (pinfunction "2_2") (pintype "passive"))
      (node (ref "R88") (pin "2") (pinfunction "2_2") (pintype "passive"))
      (node (ref "R9") (pin "2") (pinfunction "2_2") (pintype "passive"))
      (node (ref "R93") (pin "2") (pinfunction "2_2") (pintype "passive"))
      (node (ref "R94") (pin "2") (pinfunction "2_2") (pintype "passive"))
      (node (ref "R95") (pin "2") (pinfunction "2_2") (pintype "passive"))
      (node (ref "R96") (pin "2") (pinfunction "2_2") (pintype "passive"))
      (node (ref "S1") (pin "6") (pinfunction "6_6") (pintype "passive"))
      (node (ref "S10") (pin "6") (pinfunction "6_6") (pintype "passive"))
      (node (ref "S11") (pin "6") (pinfunction "6_6") (pintype "passive"))
      (node (ref "S12") (pin "6") (pinfunction "6_6") (pintype "passive"))
      (node (ref "S13") (pin "6") (pinfunction "6_6") (pintype "passive"))
      (node (ref "S14") (pin "6") (pinfunction "6_6") (pintype "passive"))
      (node (ref "S15") (pin "6") (pinfunction "6_6") (pintype "passive"))
      (node (ref "S16") (pin "6") (pinfunction "6_6") (pintype "passive"))
      (node (ref "S2") (pin "6") (pinfunction "6_6") (pintype "passive"))
      (node (ref "S3") (pin "6") (pinfunction "6_6") (pintype "passive"))
      (node (ref "S4") (pin "6") (pinfunction "6_6") (pintype "passive"))
      (node (ref "S5") (pin "6") (pinfunction "6_6") (pintype "passive"))
      (node (ref "S6") (pin "6") (pinfunction "6_6") (pintype "passive"))
      (node (ref "S7") (pin "6") (pinfunction "6_6") (pintype "passive"))
      (node (ref "S8") (pin "6") (pinfunction "6_6") (pintype "passive"))
      (node (ref "S9") (pin "6") (pinfunction "6_6") (pintype "passive"))
      (node (ref "X1") (pin "2") (pinfunction "2_2") (pintype "passive"))
      (node (ref "X1") (pin "3") (pinfunction "2_3") (pintype "passive"))
      (node (ref "X1") (pin "4") (pinfunction "2_4") (pintype "passive"))
      (node (ref "X1") (pin "5") (pinfunction "2_5") (pintype "passive"))
      (node (ref "X10") (pin "2") (pinfunction "2_2") (pintype "passive"))
      (node (ref "X10") (pin "3") (pinfunction "2_3") (pintype "passive"))
      (node (ref "X10") (pin "4") (pinfunction "2_4") (pintype "passive"))
      (node (ref "X10") (pin "5") (pinfunction "2_5") (pintype "passive"))
      (node (ref "X11") (pin "2") (pinfunction "2_2") (pintype "passive"))
      (node (ref "X11") (pin "3") (pinfunction "2_3") (pintype "passive"))
      (node (ref "X11") (pin "4") (pinfunction "2_4") (pintype "passive"))
      (node (ref "X11") (pin "5") (pinfunction "2_5") (pintype "passive"))
      (node (ref "X12") (pin "2") (pinfunction "2_2") (pintype "passive"))
      (node (ref "X12") (pin "3") (pinfunction "2_3") (pintype "passive"))
      (node (ref "X12") (pin "4") (pinfunction "2_4") (pintype "passive"))
      (node (ref "X12") (pin "5") (pinfunction "2_5") (pintype "passive"))
      (node (ref "X13") (pin "2") (pinfunction "2_2") (pintype "passive"))
      (node (ref "X13") (pin "3") (pinfunction "2_3") (pintype "passive"))
      (node (ref "X13") (pin "4") (pinfunction "2_4") (pintype "passive"))
      (node (ref "X13") (pin "5") (pinfunction "2_5") (pintype "passive"))
      (node (ref "X14") (pin "2") (pinfunction "2_2") (pintype "passive"))
      (node (ref "X14") (pin "3") (pinfunction "2_3") (pintype "passive"))
      (node (ref "X14") (pin "4") (pinfunction "2_4") (pintype "passive"))
      (node (ref "X14") (pin "5") (pinfunction "2_5") (pintype "passive"))
      (node (ref "X15") (pin "2") (pinfunction "2_2") (pintype "passive"))
      (node (ref "X15") (pin "3") (pinfunction "2_3") (pintype "passive"))
      (node (ref "X15") (pin "4") (pinfunction "2_4") (pintype "passive"))
      (node (ref "X15") (pin "5") (pinfunction "2_5") (pintype "passive"))
      (node (ref "X16") (pin "2") (pinfunction "2_2") (pintype "passive"))
      (node (ref "X16") (pin "3") (pinfunction "2_3") (pintype "passive"))
      (node (ref "X16") (pin "4") (pinfunction "2_4") (pintype "passive"))
      (node (ref "X16") (pin "5") (pinfunction "2_5") (pintype "passive"))
      (node (ref "X2") (pin "2") (pinfunction "2_2") (pintype "passive"))
      (node (ref "X2") (pin "3") (pinfunction "2_3") (pintype "passive"))
      (node (ref "X2") (pin "4") (pinfunction "2_4") (pintype "passive"))
      (node (ref "X2") (pin "5") (pinfunction "2_5") (pintype "passive"))
      (node (ref "X3") (pin "2") (pinfunction "2_2") (pintype "passive"))
      (node (ref "X3") (pin "3") (pinfunction "2_3") (pintype "passive"))
      (node (ref "X3") (pin "4") (pinfunction "2_4") (pintype "passive"))
      (node (ref "X3") (pin "5") (pinfunction "2_5") (pintype "passive"))
      (node (ref "X4") (pin "2") (pinfunction "2_2") (pintype "passive"))
      (node (ref "X4") (pin "3") (pinfunction "2_3") (pintype "passive"))
      (node (ref "X4") (pin "4") (pinfunction "2_4") (pintype "passive"))
      (node (ref "X4") (pin "5") (pinfunction "2_5") (pintype "passive"))
      (node (ref "X5") (pin "2") (pinfunction "2_2") (pintype "passive"))
      (node (ref "X5") (pin "3") (pinfunction "2_3") (pintype "passive"))
      (node (ref "X5") (pin "4") (pinfunction "2_4") (pintype "passive"))
      (node (ref "X5") (pin "5") (pinfunction "2_5") (pintype "passive"))
      (node (ref "X6") (pin "2") (pinfunction "2_2") (pintype "passive"))
      (node (ref "X6") (pin "3") (pinfunction "2_3") (pintype "passive"))
      (node (ref "X6") (pin "4") (pinfunction "2_4") (pintype "passive"))
      (node (ref "X6") (pin "5") (pinfunction "2_5") (pintype "passive"))
      (node (ref "X7") (pin "2") (pinfunction "2_2") (pintype "passive"))
      (node (ref "X7") (pin "3") (pinfunction "2_3") (pintype "passive"))
      (node (ref "X7") (pin "4") (pinfunction "2_4") (pintype "passive"))
      (node (ref "X7") (pin "5") (pinfunction "2_5") (pintype "passive"))
      (node (ref "X8") (pin "2") (pinfunction "2_2") (pintype "passive"))
      (node (ref "X8") (pin "3") (pinfunction "2_3") (pintype "passive"))
      (node (ref "X8") (pin "4") (pinfunction "2_4") (pintype "passive"))
      (node (ref "X8") (pin "5") (pinfunction "2_5") (pintype "passive"))
      (node (ref "X9") (pin "2") (pinfunction "2_2") (pintype "passive"))
      (node (ref "X9") (pin "3") (pinfunction "2_3") (pintype "passive"))
      (node (ref "X9") (pin "4") (pinfunction "2_4") (pintype "passive"))
      (node (ref "X9") (pin "5") (pinfunction "2_5") (pintype "passive"))
    )
    (net (code "55") (name "unconnected-(S1-Pad1)") (class "Default")
      (node (ref "S1") (pin "1") (pinfunction "1_1") (pintype "passive"))
    )
    (net (code "56") (name "unconnected-(S1-Pad4)") (class "Default")
      (node (ref "S1") (pin "4") (pinfunction "4_4") (pintype "passive"))
    )
    (net (code "57") (name "unconnected-(S2-Pad1)") (class "Default")
      (node (ref "S2") (pin "1") (pinfunction "1_1") (pintype "passive"))
    )
    (net (code "58") (name "unconnected-(S2-Pad4)") (class "Default")
      (node (ref "S2") (pin "4") (pinfunction "4_4") (pintype "passive"))
    )
    (net (code "59") (name "unconnected-(S3-Pad1)") (class "Default")
      (node (ref "S3") (pin "1") (pinfunction "1_1") (pintype "passive"))
    )
    (net (code "60") (name "unconnected-(S3-Pad4)") (class "Default")
      (node (ref "S3") (pin "4") (pinfunction "4_4") (pintype "passive"))
    )
    (net (code "61") (name "unconnected-(S4-Pad1)") (class "Default")
      (node (ref "S4") (pin "1") (pinfunction "1_1") (pintype "passive"))
    )
    (net (code "62") (name "unconnected-(S4-Pad4)") (class "Default")
      (node (ref "S4") (pin "4") (pinfunction "4_4") (pintype "passive"))
    )
    (net (code "63") (name "unconnected-(S5-Pad1)") (class "Default")
      (node (ref "S5") (pin "1") (pinfunction "1_1") (pintype "passive"))
    )
    (net (code "64") (name "unconnected-(S5-Pad4)") (class "Default")
      (node (ref "S5") (pin "4") (pinfunction "4_4") (pintype "passive"))
    )
    (net (code "65") (name "unconnected-(S6-Pad1)") (class "Default")
      (node (ref "S6") (pin "1") (pinfunction "1_1") (pintype "passive"))
    )
    (net (code "66") (name "unconnected-(S6-Pad4)") (class "Default")
      (node (ref "S6") (pin "4") (pinfunction "4_4") (pintype "passive"))
    )
    (net (code "67") (name "unconnected-(S7-Pad1)") (class "Default")
      (node (ref "S7") (pin "1") (pinfunction "1_1") (pintype "passive"))
    )
    (net (code "68") (name "unconnected-(S7-Pad4)") (class "Default")
      (node (ref "S7") (pin "4") (pinfunction "4_4") (pintype "passive"))
    )
    (net (code "69") (name "unconnected-(S8-Pad1)") (class "Default")
      (node (ref "S8") (pin "1") (pinfunction "1_1") (pintype "passive"))
    )
    (net (code "70") (name "unconnected-(S8-Pad4)") (class "Default")
      (node (ref "S8") (pin "4") (pinfunction "4_4") (pintype "passive"))
    )
    (net (code "71") (name "unconnected-(S9-Pad1)") (class "Default")
      (node (ref "S9") (pin "1") (pinfunction "1_1") (pintype "passive"))
    )
    (net (code "72") (name "unconnected-(S9-Pad4)") (class "Default")
      (node (ref "S9") (pin "4") (pinfunction "4_4") (pintype "passive"))
    )
    (net (code "73") (name "unconnected-(S10-Pad1)") (class "Default")
      (node (ref "S10") (pin "1") (pinfunction "1_1") (pintype "passive"))
    )
    (net (code "74") (name "unconnected-(S10-Pad4)") (class "Default")
      (node (ref "S10") (pin "4") (pinfunction "4_4") (pintype "passive"))
    )
    (net (code "75") (name "unconnected-(S11-Pad1)") (class "Default")
      (node (ref "S11") (pin "1") (pinfunction "1_1") (pintype "passive"))
    )
    (net (code "76") (name "unconnected-(S11-Pad4)") (class "Default")
      (node (ref "S11") (pin "4") (pinfunction "4_4") (pintype "passive"))
    )
    (net (code "77") (name "unconnected-(S12-Pad1)") (class "Default")
      (node (ref "S12") (pin "1") (pinfunction "1_1") (pintype "passive"))
    )
    (net (code "78") (name "unconnected-(S12-Pad4)") (class "Default")
      (node (ref "S12") (pin "4") (pinfunction "4_4") (pintype "passive"))
    )
    (net (code "79") (name "unconnected-(S13-Pad1)") (class "Default")
      (node (ref "S13") (pin "1") (pinfunction "1_1") (pintype "passive"))
    )
    (net (code "80") (name "unconnected-(S13-Pad4)") (class "Default")
      (node (ref "S13") (pin "4") (pinfunction "4_4") (pintype "passive"))
    )
    (net (code "81") (name "unconnected-(S14-Pad1)") (class "Default")
      (node (ref "S14") (pin "1") (pinfunction "1_1") (pintype "passive"))
    )
    (net (code "82") (name "unconnected-(S14-Pad4)") (class "Default")
      (node (ref "S14") (pin "4") (pinfunction "4_4") (pintype "passive"))
    )
    (net (code "83") (name "unconnected-(S15-Pad1)") (class "Default")
      (node (ref "S15") (pin "1") (pinfunction "1_1") (pintype "passive"))
    )
    (net (code "84") (name "unconnected-(S15-Pad4)") (class "Default")
      (node (ref "S15") (pin "4") (pinfunction "4_4") (pintype "passive"))
    )
    (net (code "85") (name "unconnected-(S16-Pad1)") (class "Default")
      (node (ref "S16") (pin "1") (pinfunction "1_1") (pintype "passive"))
    )
    (net (code "86") (name "unconnected-(S16-Pad4)") (class "Default")
      (node (ref "S16") (pin "4") (pinfunction "4_4") (pintype "passive"))
    )
  )
)
